# InWallPCB7smd.net
KiCad netlist of a schematic drawn in EAGLE
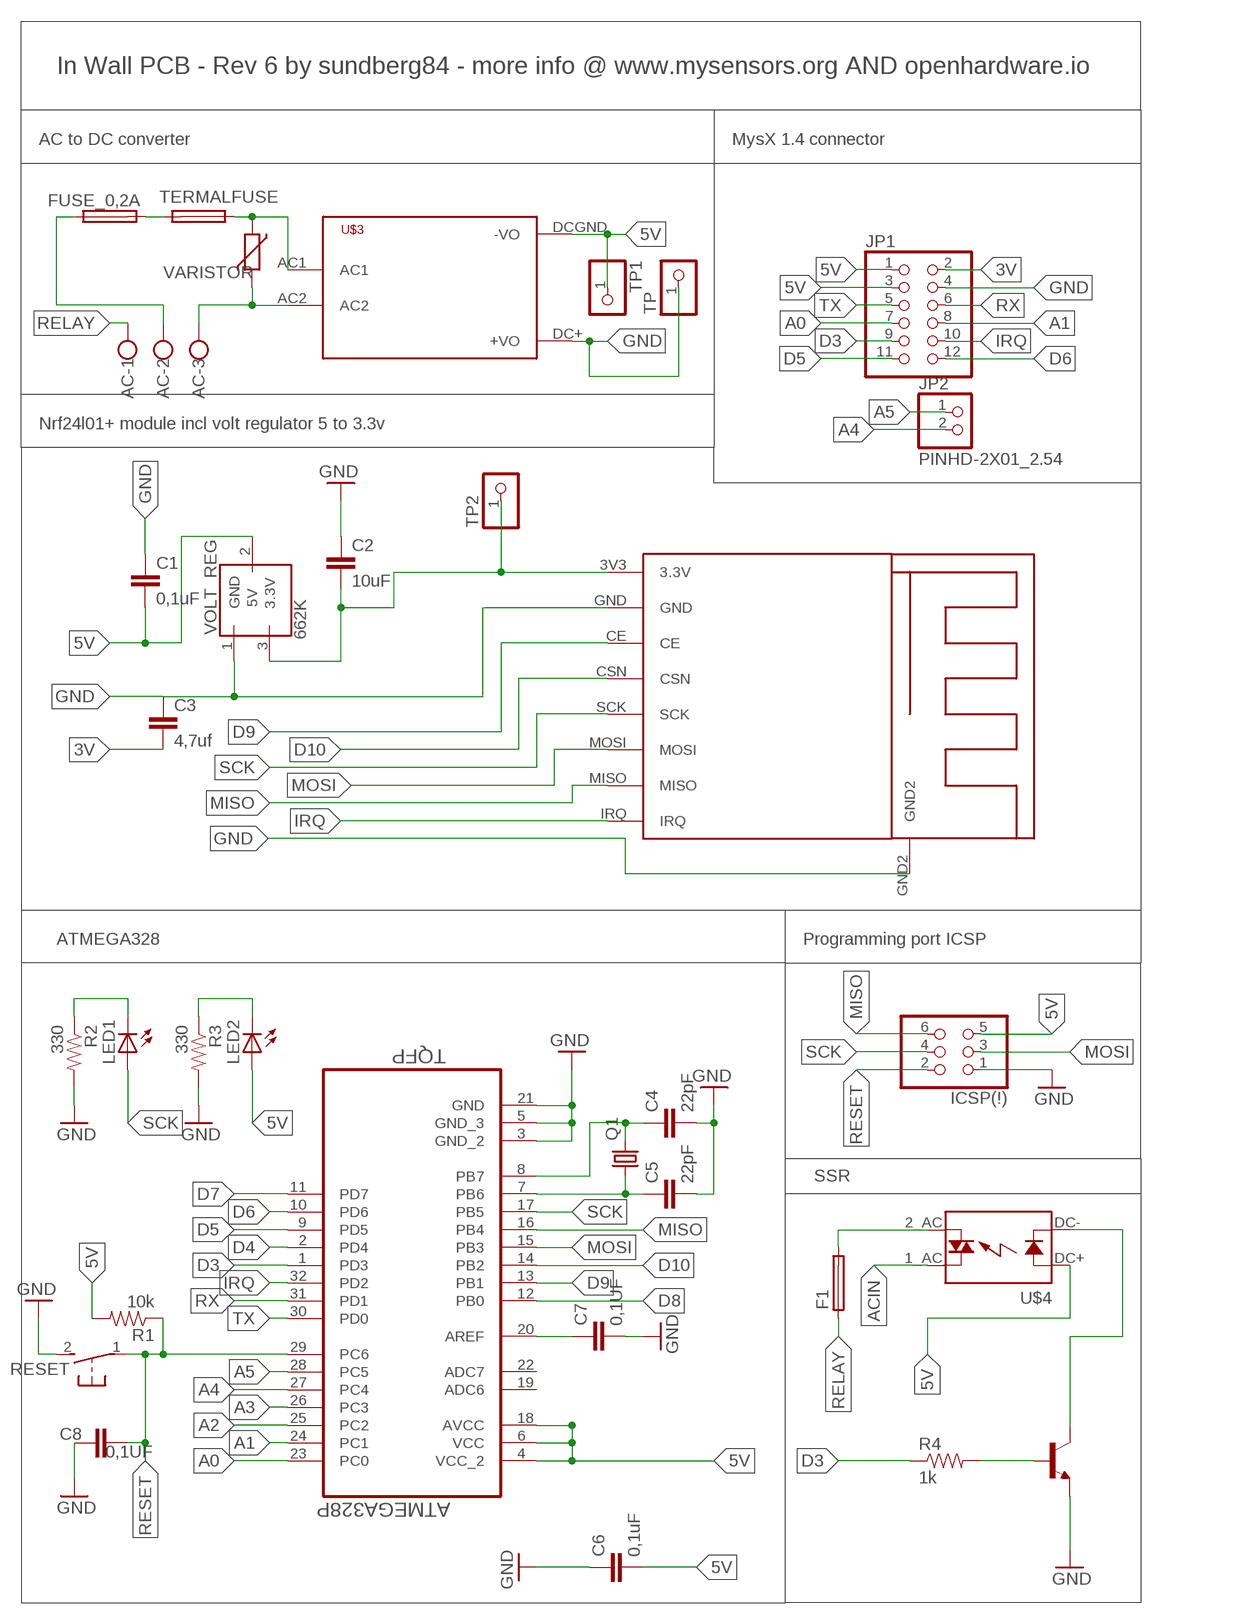
[diagram p0: schematic, sheet 1]

(export (version "E")
  (design (tool "Eeschema 10.0.6"))
  (components
    (comp (ref "AC")
      (value "W237-103")
      (footprint "eagle-import:W237-103")
      (fields (field (name "MPN") "237-103"))
      (libsource (lib "eagle-import") (part "W237-103"))
    )
    (comp (ref "ATMEGA328")
      (value "ATMEGA328P-AU")
      (footprint "eagle-import:QFP80P900X900X120-32N")
      (libsource (lib "eagle-import") (part "ATMEGA328P-AU"))
    )
    (comp (ref "C1")
      (value "0,1uF")
      (footprint "eagle-import:0805")
      (libsource (lib "eagle-import") (part "CAP0805"))
    )
    (comp (ref "C2")
      (value "10uF")
      (footprint "eagle-import:0805")
      (libsource (lib "eagle-import") (part "CAP0805"))
    )
    (comp (ref "C3")
      (value "4,7uf")
      (footprint "eagle-import:0805")
      (libsource (lib "eagle-import") (part "CAP0805"))
    )
    (comp (ref "C4")
      (value "22pF")
      (footprint "eagle-import:0805")
      (libsource (lib "eagle-import") (part "CAP0805"))
    )
    (comp (ref "C5")
      (value "22pF")
      (footprint "eagle-import:0805")
      (libsource (lib "eagle-import") (part "CAP0805"))
    )
    (comp (ref "C6")
      (value "0,1uF")
      (footprint "eagle-import:0805")
      (libsource (lib "eagle-import") (part "CAP0805"))
    )
    (comp (ref "C7")
      (value "0,1UF")
      (footprint "eagle-import:0805")
      (libsource (lib "eagle-import") (part "CAP0805"))
    )
    (comp (ref "C8")
      (value "0,1UF")
      (footprint "eagle-import:0805")
      (libsource (lib "eagle-import") (part "CAP0805"))
    )
    (comp (ref "F1")
      (value "19559")
      (footprint "eagle-import:19559")
      (fields (field (name "MPN") "55900000001"))
      (libsource (lib "eagle-import") (part "19559"))
    )
    (comp (ref "FUSE_0,2A")
      (value "FUSETE5")
      (footprint "eagle-import:TE5")
      (libsource (lib "eagle-import") (part "FUSETE5"))
    )
    (comp (ref "ICSP(!)")
      (value "PINHD-2X03_2.54")
      (footprint "eagle-import:2X03")
      (libsource (lib "eagle-import") (part "PINHD-2X03_2.54"))
    )
    (comp (ref "J3Y")
      (value "J3Y_S8050_SMD_NPN_TRANSISTOR")
      (footprint "eagle-import:SOT-23-3")
      (libsource (lib "eagle-import") (part "J3Y_S8050_SMD_NPN_TRANSISTOR"))
    )
    (comp (ref "JP1")
      (value "PINHD-2X06_2.54")
      (footprint "eagle-import:2X06")
      (libsource (lib "eagle-import") (part "PINHD-2X06_2.54"))
    )
    (comp (ref "JP2")
      (value "PINHD-2X01_2.54")
      (footprint "eagle-import:2X01")
      (libsource (lib "eagle-import") (part "PINHD-2X01_2.54"))
    )
    (comp (ref "LED1")
      (value "LEDCHIPLED_0805")
      (footprint "eagle-import:CHIPLED_0805")
      (libsource (lib "eagle-import") (part "LEDCHIPLED_0805"))
    )
    (comp (ref "LED2")
      (value "LEDCHIPLED_0805")
      (footprint "eagle-import:CHIPLED_0805")
      (libsource (lib "eagle-import") (part "LEDCHIPLED_0805"))
    )
    (comp (ref "Q1")
      (value "CRYSTALHC49S")
      (footprint "eagle-import:HC49_S")
      (libsource (lib "eagle-import") (part "CRYSTALHC49S"))
    )
    (comp (ref "R1")
      (value "10k")
      (footprint "eagle-import:0805")
      (libsource (lib "eagle-import") (part "RESISTOR0805-RES"))
    )
    (comp (ref "R2")
      (value "330")
      (footprint "eagle-import:0805")
      (libsource (lib "eagle-import") (part "RESISTOR0805-RES"))
    )
    (comp (ref "R3")
      (value "330")
      (footprint "eagle-import:0805")
      (libsource (lib "eagle-import") (part "RESISTOR0805-RES"))
    )
    (comp (ref "R4")
      (value "1k")
      (footprint "eagle-import:0805")
      (libsource (lib "eagle-import") (part "RESISTOR0805-RES"))
    )
    (comp (ref "RESET")
      (value "DTSM-3")
      (footprint "eagle-import:DTSM-3")
      (libsource (lib "eagle-import") (part "DTSM-3"))
    )
    (comp (ref "TERMALFUSE")
      (value "FUSETE5")
      (footprint "eagle-import:TE5")
      (libsource (lib "eagle-import") (part "FUSETE5"))
    )
    (comp (ref "TP")
      (value "PINHD-1X1")
      (footprint "eagle-import:1X01")
      (libsource (lib "eagle-import") (part "PINHD-1X1"))
    )
    (comp (ref "TP1")
      (value "PINHD-1X1")
      (footprint "eagle-import:1X01")
      (libsource (lib "eagle-import") (part "PINHD-1X1"))
    )
    (comp (ref "TP2")
      (value "PINHD-1X1")
      (footprint "eagle-import:1X01")
      (libsource (lib "eagle-import") (part "PINHD-1X1"))
    )
    (comp (ref "U$1")
      (value "SMD24L01+SMD")
      (footprint "eagle-import:NRF24L01+SMD")
      (libsource (lib "eagle-import") (part "SMD24L01+SMD"))
    )
    (comp (ref "U$3")
      (value "HLK-PM01")
      (footprint "eagle-import:HLK-PM01")
      (libsource (lib "eagle-import") (part "HLK-PM01"))
    )
    (comp (ref "U$4")
      (value "OMRON_G3MC-202PL_5V_SSR")
      (footprint "eagle-import:OMRON_G3MC_202PL_5V_SSR")
      (libsource (lib "eagle-import") (part "OMRON_G3MC-202PL_5V_SSR"))
    )
    (comp (ref "VARISTOR")
      (value "VARISTOR-7,5")
      (footprint "eagle-import:R-7,5")
      (libsource (lib "eagle-import") (part "VARISTOR-7,5"))
    )
    (comp (ref "VOLT_REG")
      (value "662K")
      (footprint "eagle-import:SOT-23-3")
      (libsource (lib "eagle-import") (part "662K"))
    )
  )
  (nets
    (net (code "1") (name "3V") (class "Default")
      (node (ref "C2") (pin "2") (pinfunction "2_2") (pintype "passive"))
      (node (ref "C3") (pin "2") (pinfunction "2_2") (pintype "passive"))
      (node (ref "JP1") (pin "2") (pinfunction "2_2") (pintype "passive"))
      (node (ref "TP2") (pin "1") (pinfunction "1_1") (pintype "passive"))
      (node (ref "U$1") (pin "3V3") (pinfunction "3.3V_3V3") (pintype "bidirectional"))
      (node (ref "VOLT_REG") (pin "3") (pinfunction "3.3V_3") (pintype "bidirectional"))
    )
    (net (code "2") (name "5V") (class "Default")
      (node (ref "ATMEGA328") (pin "18") (pinfunction "AVCC_18") (pintype "power_in"))
      (node (ref "ATMEGA328") (pin "4") (pinfunction "VCC_2_4") (pintype "power_in"))
      (node (ref "ATMEGA328") (pin "6") (pinfunction "VCC_6") (pintype "power_in"))
      (node (ref "C1") (pin "2") (pinfunction "2_2") (pintype "passive"))
      (node (ref "C6") (pin "2") (pinfunction "2_2") (pintype "passive"))
      (node (ref "ICSP(!)") (pin "5") (pinfunction "5_5") (pintype "passive"))
      (node (ref "JP1") (pin "1") (pinfunction "1_1") (pintype "passive"))
      (node (ref "JP1") (pin "3") (pinfunction "3_3") (pintype "passive"))
      (node (ref "LED2") (pin "A") (pinfunction "A_A") (pintype "passive"))
      (node (ref "R1") (pin "2") (pinfunction "2_2") (pintype "passive"))
      (node (ref "TP1") (pin "1") (pinfunction "1_1") (pintype "passive"))
      (node (ref "U$3") (pin "DCGND") (pinfunction "-VO_DCGND") (pintype "bidirectional"))
      (node (ref "U$4") (pin "DC+") (pinfunction "DCSIGNAL_DC+") (pintype "passive"))
      (node (ref "VOLT_REG") (pin "2") (pinfunction "5V_2") (pintype "bidirectional"))
    )
    (net (code "3") (name "A0") (class "Default")
      (node (ref "ATMEGA328") (pin "23") (pinfunction "PC0_23") (pintype "bidirectional"))
      (node (ref "JP1") (pin "7") (pinfunction "7_7") (pintype "passive"))
    )
    (net (code "4") (name "A1") (class "Default")
      (node (ref "ATMEGA328") (pin "24") (pinfunction "PC1_24") (pintype "bidirectional"))
      (node (ref "JP1") (pin "8") (pinfunction "8_8") (pintype "passive"))
    )
    (net (code "5") (name "A2") (class "Default")
      (node (ref "ATMEGA328") (pin "25") (pinfunction "PC2_25") (pintype "bidirectional"))
    )
    (net (code "6") (name "A3") (class "Default")
      (node (ref "ATMEGA328") (pin "26") (pinfunction "PC3_26") (pintype "bidirectional"))
    )
    (net (code "7") (name "A4") (class "Default")
      (node (ref "ATMEGA328") (pin "27") (pinfunction "PC4_27") (pintype "bidirectional"))
      (node (ref "JP2") (pin "2") (pinfunction "2_2") (pintype "passive"))
    )
    (net (code "8") (name "A5") (class "Default")
      (node (ref "ATMEGA328") (pin "28") (pinfunction "PC5_28") (pintype "bidirectional"))
      (node (ref "JP2") (pin "1") (pinfunction "1_1") (pintype "passive"))
    )
    (net (code "9") (name "ACIN") (class "Default")
      (node (ref "AC") (pin "2") (pinfunction "KL_2") (pintype "passive"))
      (node (ref "FUSE_0,2A") (pin "1") (pinfunction "1_1") (pintype "passive"))
      (node (ref "U$4") (pin "1_AC") (pinfunction "HOT_1_AC") (pintype "passive"))
    )
    (net (code "10") (name "D3") (class "Default")
      (node (ref "ATMEGA328") (pin "1") (pinfunction "PD3_1") (pintype "bidirectional"))
      (node (ref "JP1") (pin "9") (pinfunction "9_9") (pintype "passive"))
      (node (ref "R4") (pin "1") (pinfunction "1_1") (pintype "passive"))
    )
    (net (code "11") (name "D4") (class "Default")
      (node (ref "ATMEGA328") (pin "2") (pinfunction "PD4_2") (pintype "bidirectional"))
    )
    (net (code "12") (name "D5") (class "Default")
      (node (ref "ATMEGA328") (pin "9") (pinfunction "PD5_9") (pintype "bidirectional"))
      (node (ref "JP1") (pin "11") (pinfunction "11_11") (pintype "passive"))
    )
    (net (code "13") (name "D6") (class "Default")
      (node (ref "ATMEGA328") (pin "10") (pinfunction "PD6_10") (pintype "bidirectional"))
      (node (ref "JP1") (pin "12") (pinfunction "12_12") (pintype "passive"))
    )
    (net (code "14") (name "D7") (class "Default")
      (node (ref "ATMEGA328") (pin "11") (pinfunction "PD7_11") (pintype "bidirectional"))
    )
    (net (code "15") (name "D8") (class "Default")
      (node (ref "ATMEGA328") (pin "12") (pinfunction "PB0_12") (pintype "bidirectional"))
    )
    (net (code "16") (name "D9") (class "Default")
      (node (ref "ATMEGA328") (pin "13") (pinfunction "PB1_13") (pintype "bidirectional"))
      (node (ref "U$1") (pin "CE") (pinfunction "CE_CE") (pintype "bidirectional"))
    )
    (net (code "17") (name "D10") (class "Default")
      (node (ref "ATMEGA328") (pin "14") (pinfunction "PB2_14") (pintype "bidirectional"))
      (node (ref "U$1") (pin "CSN") (pinfunction "CSN_CSN") (pintype "bidirectional"))
    )
    (net (code "18") (name "GND") (class "Default")
      (node (ref "ATMEGA328") (pin "21") (pinfunction "GND_21") (pintype "passive"))
      (node (ref "ATMEGA328") (pin "3") (pinfunction "GND_2_3") (pintype "passive"))
      (node (ref "ATMEGA328") (pin "5") (pinfunction "GND_3_5") (pintype "passive"))
      (node (ref "C1") (pin "1") (pinfunction "1_1") (pintype "passive"))
      (node (ref "C2") (pin "1") (pinfunction "1_1") (pintype "passive"))
      (node (ref "C3") (pin "1") (pinfunction "1_1") (pintype "passive"))
      (node (ref "C4") (pin "2") (pinfunction "2_2") (pintype "passive"))
      (node (ref "C5") (pin "2") (pinfunction "2_2") (pintype "passive"))
      (node (ref "C6") (pin "1") (pinfunction "1_1") (pintype "passive"))
      (node (ref "C7") (pin "2") (pinfunction "2_2") (pintype "passive"))
      (node (ref "C8") (pin "1") (pinfunction "1_1") (pintype "passive"))
      (node (ref "ICSP(!)") (pin "1") (pinfunction "1_1") (pintype "passive"))
      (node (ref "J3Y") (pin "3") (pinfunction "E_3") (pintype "passive"))
      (node (ref "JP1") (pin "4") (pinfunction "4_4") (pintype "passive"))
      (node (ref "R2") (pin "2") (pinfunction "2_2") (pintype "passive"))
      (node (ref "R3") (pin "2") (pinfunction "2_2") (pintype "passive"))
      (node (ref "RESET") (pin "2") (pinfunction "2_2") (pintype "passive"))
      (node (ref "TP") (pin "1") (pinfunction "1_1") (pintype "passive"))
      (node (ref "U$1") (pin "GND") (pinfunction "GND_GND") (pintype "bidirectional"))
      (node (ref "U$1") (pin "GND2") (pinfunction "GND2_GND2") (pintype "bidirectional"))
      (node (ref "U$3") (pin "DC+") (pinfunction "+VO_DC+") (pintype "bidirectional"))
      (node (ref "VOLT_REG") (pin "1") (pinfunction "GND_1") (pintype "bidirectional"))
    )
    (net (code "19") (name "IRQ") (class "Default")
      (node (ref "ATMEGA328") (pin "32") (pinfunction "PD2_32") (pintype "bidirectional"))
      (node (ref "JP1") (pin "10") (pinfunction "10_10") (pintype "passive"))
      (node (ref "U$1") (pin "IRQ") (pinfunction "IRQ_IRQ") (pintype "bidirectional"))
    )
    (net (code "20") (name "MISO") (class "Default")
      (node (ref "ATMEGA328") (pin "16") (pinfunction "PB4_16") (pintype "bidirectional"))
      (node (ref "ICSP(!)") (pin "6") (pinfunction "6_6") (pintype "passive"))
      (node (ref "U$1") (pin "MISO") (pinfunction "MISO_MISO") (pintype "bidirectional"))
    )
    (net (code "21") (name "MOSI") (class "Default")
      (node (ref "ATMEGA328") (pin "15") (pinfunction "PB3_15") (pintype "bidirectional"))
      (node (ref "ICSP(!)") (pin "3") (pinfunction "3_3") (pintype "passive"))
      (node (ref "U$1") (pin "MOSI") (pinfunction "MOSI_MOSI") (pintype "bidirectional"))
    )
    (net (code "22") (name "Net-(ACC-KL)") (class "Default")
      (node (ref "AC") (pin "3") (pinfunction "KL_3") (pintype "passive"))
      (node (ref "U$3") (pin "AC2") (pinfunction "AC2_AC2") (pintype "bidirectional"))
      (node (ref "VARISTOR") (pin "2") (pinfunction "2_2") (pintype "passive"))
    )
    (net (code "23") (name "Net-(ATMEGA328-AREF)") (class "Default")
      (node (ref "ATMEGA328") (pin "20") (pinfunction "AREF_20") (pintype "input"))
      (node (ref "C7") (pin "1") (pinfunction "1_1") (pintype "passive"))
    )
    (net (code "24") (name "Net-(ATMEGA328-PB6)") (class "Default")
      (node (ref "ATMEGA328") (pin "7") (pinfunction "PB6_7") (pintype "bidirectional"))
      (node (ref "C5") (pin "1") (pinfunction "1_1") (pintype "passive"))
      (node (ref "Q1") (pin "1") (pinfunction "1_1") (pintype "passive"))
    )
    (net (code "25") (name "Net-(ATMEGA328-PB7)") (class "Default")
      (node (ref "ATMEGA328") (pin "8") (pinfunction "PB7_8") (pintype "bidirectional"))
      (node (ref "C4") (pin "1") (pinfunction "1_1") (pintype "passive"))
      (node (ref "Q1") (pin "2") (pinfunction "2_2") (pintype "passive"))
    )
    (net (code "26") (name "Net-(FUSE_0,2A-Pad2)") (class "Default")
      (node (ref "FUSE_0,2A") (pin "2") (pinfunction "2_2") (pintype "passive"))
      (node (ref "TERMALFUSE") (pin "2") (pinfunction "2_2") (pintype "passive"))
    )
    (net (code "27") (name "Net-(J3Y-B)") (class "Default")
      (node (ref "J3Y") (pin "1") (pinfunction "B_1") (pintype "passive"))
      (node (ref "R4") (pin "2") (pinfunction "2_2") (pintype "passive"))
    )
    (net (code "28") (name "Net-(J3Y-C)") (class "Default")
      (node (ref "J3Y") (pin "2") (pinfunction "C_2") (pintype "passive"))
      (node (ref "U$4") (pin "DC-") (pinfunction "DCGND_DC-") (pintype "passive"))
    )
    (net (code "29") (name "Net-(LED1-PadC)") (class "Default")
      (node (ref "LED1") (pin "C") (pinfunction "C_C") (pintype "passive"))
      (node (ref "R2") (pin "1") (pinfunction "1_1") (pintype "passive"))
    )
    (net (code "30") (name "Net-(LED2-PadC)") (class "Default")
      (node (ref "LED2") (pin "C") (pinfunction "C_C") (pintype "passive"))
      (node (ref "R3") (pin "1") (pinfunction "1_1") (pintype "passive"))
    )
    (net (code "31") (name "Net-(TERMALFUSE-Pad1)") (class "Default")
      (node (ref "TERMALFUSE") (pin "1") (pinfunction "1_1") (pintype "passive"))
      (node (ref "U$3") (pin "AC1") (pinfunction "AC1_AC1") (pintype "bidirectional"))
      (node (ref "VARISTOR") (pin "1") (pinfunction "1_1") (pintype "passive"))
    )
    (net (code "32") (name "Net-(U$4-NEUTRAL)") (class "Default")
      (node (ref "F1") (pin "2") (pinfunction "2_2") (pintype "passive"))
      (node (ref "U$4") (pin "2_AC") (pinfunction "NEUTRAL_2_AC") (pintype "passive"))
    )
    (net (code "33") (name "RELAY") (class "Default")
      (node (ref "AC") (pin "1") (pinfunction "KL_1") (pintype "passive"))
      (node (ref "F1") (pin "1") (pinfunction "1_1") (pintype "passive"))
    )
    (net (code "34") (name "RESET") (class "Default")
      (node (ref "ATMEGA328") (pin "29") (pinfunction "PC6_29") (pintype "bidirectional"))
      (node (ref "C8") (pin "2") (pinfunction "2_2") (pintype "passive"))
      (node (ref "ICSP(!)") (pin "2") (pinfunction "2_2") (pintype "passive"))
      (node (ref "R1") (pin "1") (pinfunction "1_1") (pintype "passive"))
      (node (ref "RESET") (pin "1") (pinfunction "1_1") (pintype "passive"))
    )
    (net (code "35") (name "RX") (class "Default")
      (node (ref "ATMEGA328") (pin "31") (pinfunction "PD1_31") (pintype "bidirectional"))
      (node (ref "JP1") (pin "6") (pinfunction "6_6") (pintype "passive"))
    )
    (net (code "36") (name "SCK") (class "Default")
      (node (ref "ATMEGA328") (pin "17") (pinfunction "PB5_17") (pintype "bidirectional"))
      (node (ref "ICSP(!)") (pin "4") (pinfunction "4_4") (pintype "passive"))
      (node (ref "LED1") (pin "A") (pinfunction "A_A") (pintype "passive"))
      (node (ref "U$1") (pin "SCK") (pinfunction "SCK_SCK") (pintype "bidirectional"))
    )
    (net (code "37") (name "TX") (class "Default")
      (node (ref "ATMEGA328") (pin "30") (pinfunction "PD0_30") (pintype "bidirectional"))
      (node (ref "JP1") (pin "5") (pinfunction "5_5") (pintype "passive"))
    )
    (net (code "38") (name "unconnected-(ATMEGA328-ADC6-Pad19)") (class "Default")
      (node (ref "ATMEGA328") (pin "19") (pinfunction "ADC6_19") (pintype "input"))
    )
    (net (code "39") (name "unconnected-(ATMEGA328-ADC7-Pad22)") (class "Default")
      (node (ref "ATMEGA328") (pin "22") (pinfunction "ADC7_22") (pintype "input"))
    )
  )
)
